# BLE113_breakout.net
KiCad netlist of a schematic drawn in EAGLE
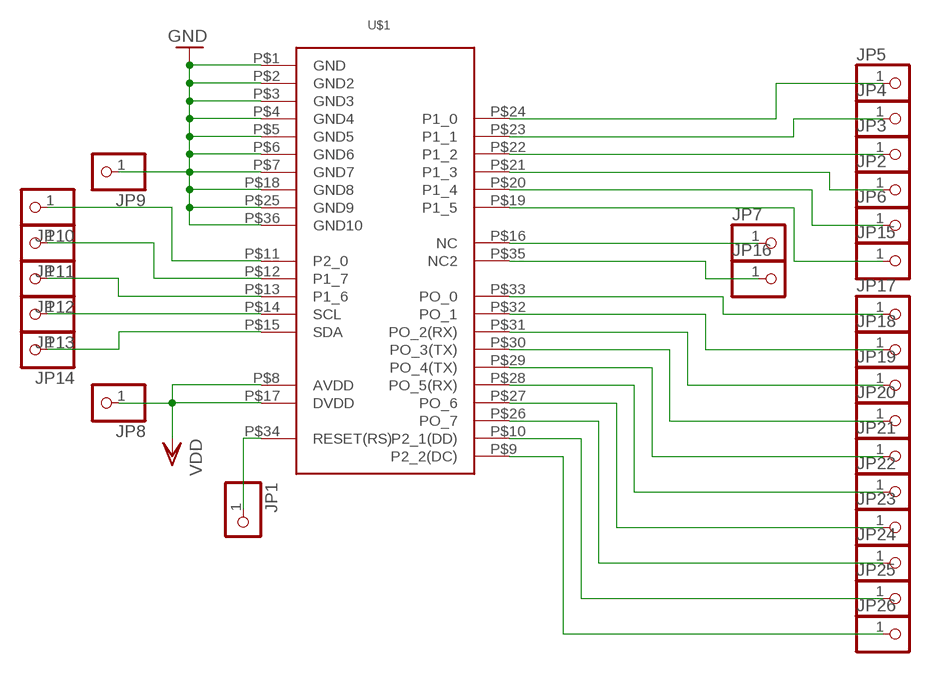
[diagram p0: schematic, sheet 1]

(export (version "E")
  (design (tool "Eeschema 10.0.6"))
  (components
    (comp (ref "JP1")
      (value "PINHD-1X1")
      (footprint "eagle-import:1X01")
      (libsource (lib "eagle-import") (part "PINHD-1X1"))
    )
    (comp (ref "JP2")
      (value "PINHD-1X1")
      (footprint "eagle-import:1X01")
      (libsource (lib "eagle-import") (part "PINHD-1X1"))
    )
    (comp (ref "JP3")
      (value "PINHD-1X1")
      (footprint "eagle-import:1X01")
      (libsource (lib "eagle-import") (part "PINHD-1X1"))
    )
    (comp (ref "JP4")
      (value "PINHD-1X1")
      (footprint "eagle-import:1X01")
      (libsource (lib "eagle-import") (part "PINHD-1X1"))
    )
    (comp (ref "JP5")
      (value "PINHD-1X1")
      (footprint "eagle-import:1X01")
      (libsource (lib "eagle-import") (part "PINHD-1X1"))
    )
    (comp (ref "JP6")
      (value "PINHD-1X1")
      (footprint "eagle-import:1X01")
      (libsource (lib "eagle-import") (part "PINHD-1X1"))
    )
    (comp (ref "JP7")
      (value "PINHD-1X1")
      (footprint "eagle-import:1X01")
      (libsource (lib "eagle-import") (part "PINHD-1X1"))
    )
    (comp (ref "JP8")
      (value "PINHD-1X1")
      (footprint "eagle-import:1X01")
      (libsource (lib "eagle-import") (part "PINHD-1X1"))
    )
    (comp (ref "JP9")
      (value "PINHD-1X1")
      (footprint "eagle-import:1X01")
      (libsource (lib "eagle-import") (part "PINHD-1X1"))
    )
    (comp (ref "JP10")
      (value "PINHD-1X1")
      (footprint "eagle-import:1X01")
      (libsource (lib "eagle-import") (part "PINHD-1X1"))
    )
    (comp (ref "JP11")
      (value "PINHD-1X1")
      (footprint "eagle-import:1X01")
      (libsource (lib "eagle-import") (part "PINHD-1X1"))
    )
    (comp (ref "JP12")
      (value "PINHD-1X1")
      (footprint "eagle-import:1X01")
      (libsource (lib "eagle-import") (part "PINHD-1X1"))
    )
    (comp (ref "JP13")
      (value "PINHD-1X1")
      (footprint "eagle-import:1X01")
      (libsource (lib "eagle-import") (part "PINHD-1X1"))
    )
    (comp (ref "JP14")
      (value "PINHD-1X1")
      (footprint "eagle-import:1X01")
      (libsource (lib "eagle-import") (part "PINHD-1X1"))
    )
    (comp (ref "JP15")
      (value "PINHD-1X1")
      (footprint "eagle-import:1X01")
      (libsource (lib "eagle-import") (part "PINHD-1X1"))
    )
    (comp (ref "JP16")
      (value "PINHD-1X1")
      (footprint "eagle-import:1X01")
      (libsource (lib "eagle-import") (part "PINHD-1X1"))
    )
    (comp (ref "JP17")
      (value "PINHD-1X1")
      (footprint "eagle-import:1X01")
      (libsource (lib "eagle-import") (part "PINHD-1X1"))
    )
    (comp (ref "JP18")
      (value "PINHD-1X1")
      (footprint "eagle-import:1X01")
      (libsource (lib "eagle-import") (part "PINHD-1X1"))
    )
    (comp (ref "JP19")
      (value "PINHD-1X1")
      (footprint "eagle-import:1X01")
      (libsource (lib "eagle-import") (part "PINHD-1X1"))
    )
    (comp (ref "JP20")
      (value "PINHD-1X1")
      (footprint "eagle-import:1X01")
      (libsource (lib "eagle-import") (part "PINHD-1X1"))
    )
    (comp (ref "JP21")
      (value "PINHD-1X1")
      (footprint "eagle-import:1X01")
      (libsource (lib "eagle-import") (part "PINHD-1X1"))
    )
    (comp (ref "JP22")
      (value "PINHD-1X1")
      (footprint "eagle-import:1X01")
      (libsource (lib "eagle-import") (part "PINHD-1X1"))
    )
    (comp (ref "JP23")
      (value "PINHD-1X1")
      (footprint "eagle-import:1X01")
      (libsource (lib "eagle-import") (part "PINHD-1X1"))
    )
    (comp (ref "JP24")
      (value "PINHD-1X1")
      (footprint "eagle-import:1X01")
      (libsource (lib "eagle-import") (part "PINHD-1X1"))
    )
    (comp (ref "JP25")
      (value "PINHD-1X1")
      (footprint "eagle-import:1X01")
      (libsource (lib "eagle-import") (part "PINHD-1X1"))
    )
    (comp (ref "JP26")
      (value "PINHD-1X1")
      (footprint "eagle-import:1X01")
      (libsource (lib "eagle-import") (part "PINHD-1X1"))
    )
    (comp (ref "U$1")
      (value "BLE113-A")
      (footprint "eagle-import:BLUETOOTHNS")
      (libsource (lib "eagle-import") (part "BLE113-A"))
    )
  )
  (nets
    (net (code "1") (name "GND") (class "Default")
      (node (ref "JP9") (pin "1") (pinfunction "1_1") (pintype "passive"))
      (node (ref "U$1") (pin "P$1") (pinfunction "GND_P$1") (pintype "bidirectional"))
      (node (ref "U$1") (pin "P$18") (pinfunction "GND8_P$18") (pintype "bidirectional"))
      (node (ref "U$1") (pin "P$2") (pinfunction "GND2_P$2") (pintype "bidirectional"))
      (node (ref "U$1") (pin "P$25") (pinfunction "GND9_P$25") (pintype "bidirectional"))
      (node (ref "U$1") (pin "P$3") (pinfunction "GND3_P$3") (pintype "bidirectional"))
      (node (ref "U$1") (pin "P$36") (pinfunction "GND10_P$36") (pintype "bidirectional"))
      (node (ref "U$1") (pin "P$4") (pinfunction "GND4_P$4") (pintype "bidirectional"))
      (node (ref "U$1") (pin "P$5") (pinfunction "GND5_P$5") (pintype "bidirectional"))
      (node (ref "U$1") (pin "P$6") (pinfunction "GND6_P$6") (pintype "bidirectional"))
      (node (ref "U$1") (pin "P$7") (pinfunction "GND7_P$7") (pintype "bidirectional"))
    )
    (net (code "2") (name "Net-(U$1-NC)") (class "Default")
      (node (ref "JP7") (pin "1") (pinfunction "1_1") (pintype "passive"))
      (node (ref "U$1") (pin "P$16") (pinfunction "NC_P$16") (pintype "bidirectional"))
    )
    (net (code "3") (name "Net-(U$1-NC2)") (class "Default")
      (node (ref "JP16") (pin "1") (pinfunction "1_1") (pintype "passive"))
      (node (ref "U$1") (pin "P$35") (pinfunction "NC2_P$35") (pintype "bidirectional"))
    )
    (net (code "4") (name "Net-(U$1-P1_0)") (class "Default")
      (node (ref "JP5") (pin "1") (pinfunction "1_1") (pintype "passive"))
      (node (ref "U$1") (pin "P$24") (pinfunction "P1_0_P$24") (pintype "bidirectional"))
    )
    (net (code "5") (name "Net-(U$1-P1_1)") (class "Default")
      (node (ref "JP4") (pin "1") (pinfunction "1_1") (pintype "passive"))
      (node (ref "U$1") (pin "P$23") (pinfunction "P1_1_P$23") (pintype "bidirectional"))
    )
    (net (code "6") (name "Net-(U$1-P1_2)") (class "Default")
      (node (ref "JP3") (pin "1") (pinfunction "1_1") (pintype "passive"))
      (node (ref "U$1") (pin "P$22") (pinfunction "P1_2_P$22") (pintype "bidirectional"))
    )
    (net (code "7") (name "Net-(U$1-P1_3)") (class "Default")
      (node (ref "JP2") (pin "1") (pinfunction "1_1") (pintype "passive"))
      (node (ref "U$1") (pin "P$21") (pinfunction "P1_3_P$21") (pintype "bidirectional"))
    )
    (net (code "8") (name "Net-(U$1-P1_4)") (class "Default")
      (node (ref "JP6") (pin "1") (pinfunction "1_1") (pintype "passive"))
      (node (ref "U$1") (pin "P$20") (pinfunction "P1_4_P$20") (pintype "bidirectional"))
    )
    (net (code "9") (name "Net-(U$1-P1_5)") (class "Default")
      (node (ref "JP15") (pin "1") (pinfunction "1_1") (pintype "passive"))
      (node (ref "U$1") (pin "P$19") (pinfunction "P1_5_P$19") (pintype "bidirectional"))
    )
    (net (code "10") (name "Net-(U$1-P1_6)") (class "Default")
      (node (ref "JP12") (pin "1") (pinfunction "1_1") (pintype "passive"))
      (node (ref "U$1") (pin "P$13") (pinfunction "P1_6_P$13") (pintype "bidirectional"))
    )
    (net (code "11") (name "Net-(U$1-P1_7)") (class "Default")
      (node (ref "JP11") (pin "1") (pinfunction "1_1") (pintype "passive"))
      (node (ref "U$1") (pin "P$12") (pinfunction "P1_7_P$12") (pintype "bidirectional"))
    )
    (net (code "12") (name "Net-(U$1-P2_0)") (class "Default")
      (node (ref "JP10") (pin "1") (pinfunction "1_1") (pintype "passive"))
      (node (ref "U$1") (pin "P$11") (pinfunction "P2_0_P$11") (pintype "bidirectional"))
    )
    (net (code "13") (name "Net-(U$1-P2_1(DD))") (class "Default")
      (node (ref "JP25") (pin "1") (pinfunction "1_1") (pintype "passive"))
      (node (ref "U$1") (pin "P$10") (pinfunction "P2_1(DD)_P$10") (pintype "bidirectional"))
    )
    (net (code "14") (name "Net-(U$1-P2_2(DC))") (class "Default")
      (node (ref "JP26") (pin "1") (pinfunction "1_1") (pintype "passive"))
      (node (ref "U$1") (pin "P$9") (pinfunction "P2_2(DC)_P$9") (pintype "bidirectional"))
    )
    (net (code "15") (name "Net-(U$1-PO_0)") (class "Default")
      (node (ref "JP17") (pin "1") (pinfunction "1_1") (pintype "passive"))
      (node (ref "U$1") (pin "P$33") (pinfunction "PO_0_P$33") (pintype "bidirectional"))
    )
    (net (code "16") (name "Net-(U$1-PO_1)") (class "Default")
      (node (ref "JP18") (pin "1") (pinfunction "1_1") (pintype "passive"))
      (node (ref "U$1") (pin "P$32") (pinfunction "PO_1_P$32") (pintype "bidirectional"))
    )
    (net (code "17") (name "Net-(U$1-PO_2(RX))") (class "Default")
      (node (ref "JP19") (pin "1") (pinfunction "1_1") (pintype "passive"))
      (node (ref "U$1") (pin "P$31") (pinfunction "PO_2(RX)_P$31") (pintype "bidirectional"))
    )
    (net (code "18") (name "Net-(U$1-PO_3(TX))") (class "Default")
      (node (ref "JP20") (pin "1") (pinfunction "1_1") (pintype "passive"))
      (node (ref "U$1") (pin "P$30") (pinfunction "PO_3(TX)_P$30") (pintype "bidirectional"))
    )
    (net (code "19") (name "Net-(U$1-PO_4(TX))") (class "Default")
      (node (ref "JP21") (pin "1") (pinfunction "1_1") (pintype "passive"))
      (node (ref "U$1") (pin "P$29") (pinfunction "PO_4(TX)_P$29") (pintype "bidirectional"))
    )
    (net (code "20") (name "Net-(U$1-PO_5(RX))") (class "Default")
      (node (ref "JP22") (pin "1") (pinfunction "1_1") (pintype "passive"))
      (node (ref "U$1") (pin "P$28") (pinfunction "PO_5(RX)_P$28") (pintype "bidirectional"))
    )
    (net (code "21") (name "Net-(U$1-PO_6)") (class "Default")
      (node (ref "JP23") (pin "1") (pinfunction "1_1") (pintype "passive"))
      (node (ref "U$1") (pin "P$27") (pinfunction "PO_6_P$27") (pintype "bidirectional"))
    )
    (net (code "22") (name "Net-(U$1-PO_7)") (class "Default")
      (node (ref "JP24") (pin "1") (pinfunction "1_1") (pintype "passive"))
      (node (ref "U$1") (pin "P$26") (pinfunction "PO_7_P$26") (pintype "bidirectional"))
    )
    (net (code "23") (name "Net-(U$1-RESET(RS))") (class "Default")
      (node (ref "JP1") (pin "1") (pinfunction "1_1") (pintype "passive"))
      (node (ref "U$1") (pin "P$34") (pinfunction "RESET(RS)_P$34") (pintype "bidirectional"))
    )
    (net (code "24") (name "Net-(U$1-SCL)") (class "Default")
      (node (ref "JP13") (pin "1") (pinfunction "1_1") (pintype "passive"))
      (node (ref "U$1") (pin "P$14") (pinfunction "SCL_P$14") (pintype "bidirectional"))
    )
    (net (code "25") (name "Net-(U$1-SDA)") (class "Default")
      (node (ref "JP14") (pin "1") (pinfunction "1_1") (pintype "passive"))
      (node (ref "U$1") (pin "P$15") (pinfunction "SDA_P$15") (pintype "bidirectional"))
    )
    (net (code "26") (name "VDD") (class "Default")
      (node (ref "JP8") (pin "1") (pinfunction "1_1") (pintype "passive"))
      (node (ref "U$1") (pin "P$17") (pinfunction "DVDD_P$17") (pintype "bidirectional"))
      (node (ref "U$1") (pin "P$8") (pinfunction "AVDD_P$8") (pintype "bidirectional"))
    )
  )
)
